# FPGA_Regulators.net
KiCad netlist of a schematic drawn in Altium Designer
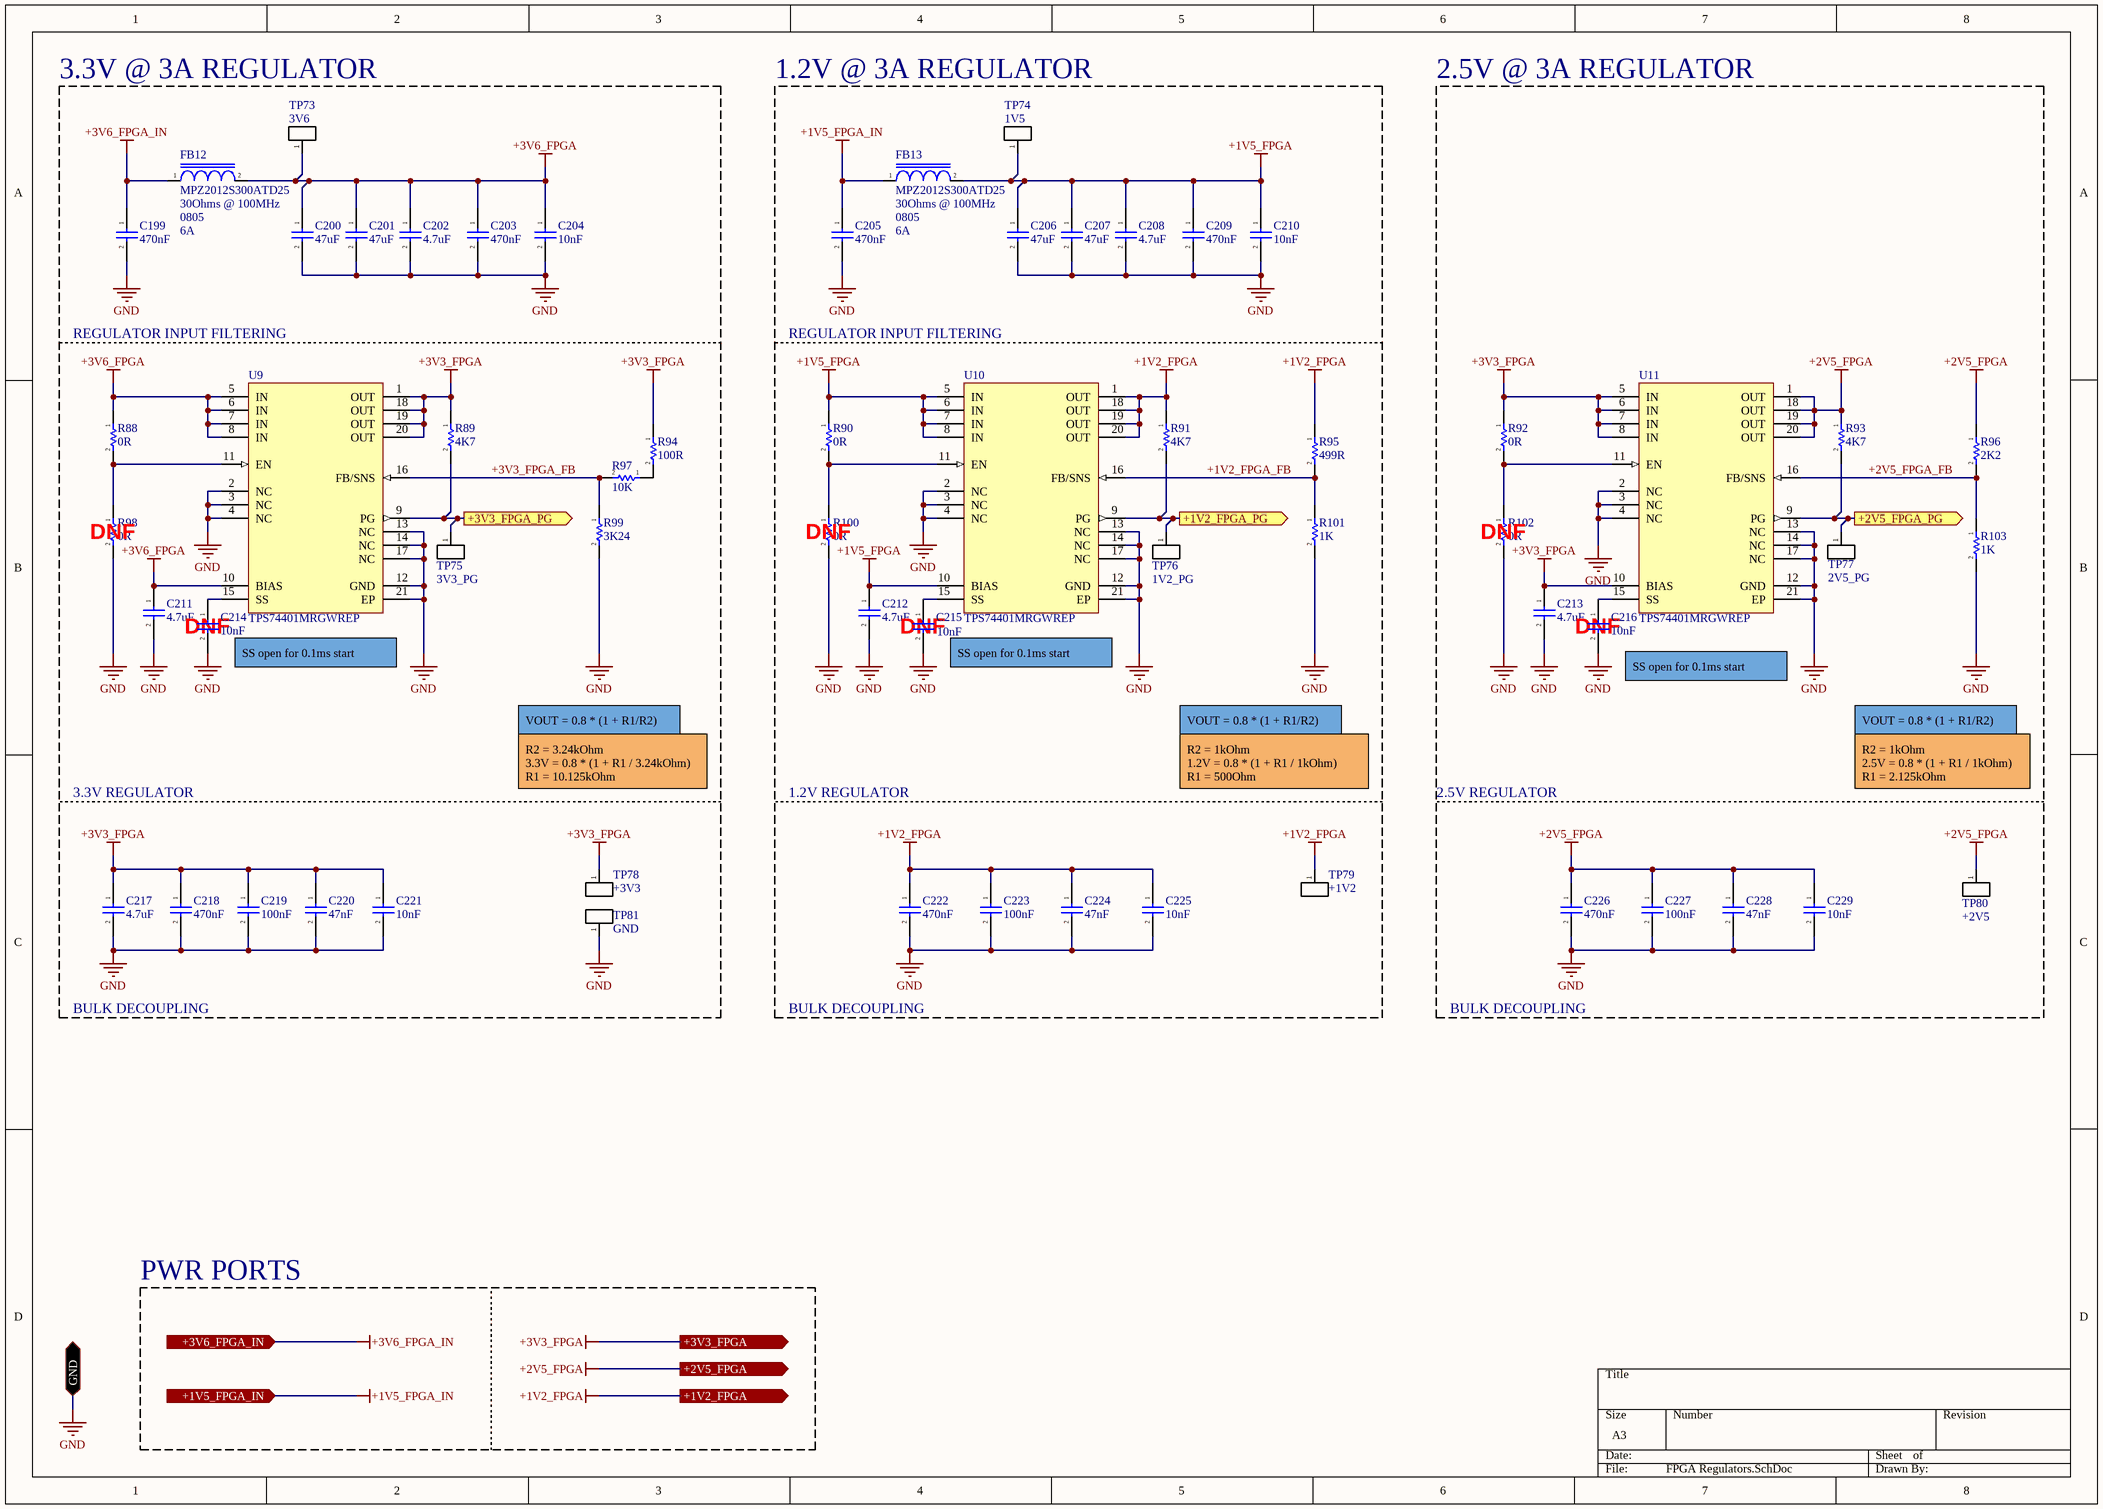
[diagram p0: FPGA Regulators.SchDoc]

(export (version "E")
  (design (tool "Eeschema 10.0.6"))
  (components
    (comp (ref "C199")
      (value "470nF")
      (footprint "CAP_0402")
      (description "Generic SMT Ceramic Capacitor")
      (libsource (lib "Symbols") (part "CAP_CER"))
    )
    (comp (ref "C200")
      (value "47uF")
      (footprint "CAP_1206")
      (description "Generic SMT Ceramic Capacitor")
      (libsource (lib "Symbols") (part "CAP_CER"))
    )
    (comp (ref "C201")
      (value "47uF")
      (footprint "CAP_1206")
      (description "Generic SMT Ceramic Capacitor")
      (libsource (lib "Symbols") (part "CAP_CER"))
    )
    (comp (ref "C202")
      (value "4.7uF")
      (footprint "CAP_0805")
      (description "Generic SMT Ceramic Capacitor")
      (libsource (lib "Symbols") (part "CAP_CER"))
    )
    (comp (ref "C203")
      (value "470nF")
      (footprint "CAP_0402")
      (description "Generic SMT Ceramic Capacitor")
      (libsource (lib "Symbols") (part "CAP_CER"))
    )
    (comp (ref "C204")
      (value "10nF")
      (footprint "CAP_0201")
      (description "Generic SMT Ceramic Capacitor")
      (libsource (lib "Symbols") (part "CAP_CER"))
    )
    (comp (ref "C205")
      (value "470nF")
      (footprint "CAP_0402")
      (description "Generic SMT Ceramic Capacitor")
      (libsource (lib "Symbols") (part "CAP_CER"))
    )
    (comp (ref "C206")
      (value "47uF")
      (footprint "CAP_1206")
      (description "Generic SMT Ceramic Capacitor")
      (libsource (lib "Symbols") (part "CAP_CER"))
    )
    (comp (ref "C207")
      (value "47uF")
      (footprint "CAP_1206")
      (description "Generic SMT Ceramic Capacitor")
      (libsource (lib "Symbols") (part "CAP_CER"))
    )
    (comp (ref "C208")
      (value "4.7uF")
      (footprint "CAP_0805")
      (description "Generic SMT Ceramic Capacitor")
      (libsource (lib "Symbols") (part "CAP_CER"))
    )
    (comp (ref "C209")
      (value "470nF")
      (footprint "CAP_0402")
      (description "Generic SMT Ceramic Capacitor")
      (libsource (lib "Symbols") (part "CAP_CER"))
    )
    (comp (ref "C210")
      (value "10nF")
      (footprint "CAP_0201")
      (description "Generic SMT Ceramic Capacitor")
      (libsource (lib "Symbols") (part "CAP_CER"))
    )
    (comp (ref "C211")
      (value "4.7uF")
      (footprint "CAP_0805")
      (description "Generic SMT Ceramic Capacitor")
      (libsource (lib "Symbols") (part "CAP_CER"))
    )
    (comp (ref "C212")
      (value "4.7uF")
      (footprint "CAP_0805")
      (description "Generic SMT Ceramic Capacitor")
      (libsource (lib "Symbols") (part "CAP_CER"))
    )
    (comp (ref "C213")
      (value "4.7uF")
      (footprint "CAP_0805")
      (description "Generic SMT Ceramic Capacitor")
      (libsource (lib "Symbols") (part "CAP_CER"))
    )
    (comp (ref "C214")
      (value "10nF")
      (footprint "CAP_0201")
      (description "Generic SMT Ceramic Capacitor")
      (libsource (lib "Symbols") (part "CAP_CER"))
    )
    (comp (ref "C215")
      (value "10nF")
      (footprint "CAP_0201")
      (description "Generic SMT Ceramic Capacitor")
      (libsource (lib "Symbols") (part "CAP_CER"))
    )
    (comp (ref "C216")
      (value "10nF")
      (footprint "CAP_0201")
      (description "Generic SMT Ceramic Capacitor")
      (libsource (lib "Symbols") (part "CAP_CER"))
    )
    (comp (ref "C217")
      (value "4.7uF")
      (footprint "CAP_0805")
      (description "Generic SMT Ceramic Capacitor")
      (libsource (lib "Symbols") (part "CAP_CER"))
    )
    (comp (ref "C218")
      (value "470nF")
      (footprint "CAP_0402")
      (description "Generic SMT Ceramic Capacitor")
      (libsource (lib "Symbols") (part "CAP_CER"))
    )
    (comp (ref "C219")
      (value "100nF")
      (footprint "CAP_0402")
      (description "Generic SMT Ceramic Capacitor")
      (libsource (lib "Symbols") (part "CAP_CER"))
    )
    (comp (ref "C220")
      (value "47nF")
      (footprint "CAP_0201")
      (description "Generic SMT Ceramic Capacitor")
      (libsource (lib "Symbols") (part "CAP_CER"))
    )
    (comp (ref "C221")
      (value "10nF")
      (footprint "CAP_0201")
      (description "Generic SMT Ceramic Capacitor")
      (libsource (lib "Symbols") (part "CAP_CER"))
    )
    (comp (ref "C222")
      (value "470nF")
      (footprint "CAP_0402")
      (description "Generic SMT Ceramic Capacitor")
      (libsource (lib "Symbols") (part "CAP_CER"))
    )
    (comp (ref "C223")
      (value "100nF")
      (footprint "CAP_0402")
      (description "Generic SMT Ceramic Capacitor")
      (libsource (lib "Symbols") (part "CAP_CER"))
    )
    (comp (ref "C224")
      (value "47nF")
      (footprint "CAP_0201")
      (description "Generic SMT Ceramic Capacitor")
      (libsource (lib "Symbols") (part "CAP_CER"))
    )
    (comp (ref "C225")
      (value "10nF")
      (footprint "CAP_0201")
      (description "Generic SMT Ceramic Capacitor")
      (libsource (lib "Symbols") (part "CAP_CER"))
    )
    (comp (ref "C226")
      (value "470nF")
      (footprint "CAP_0402")
      (description "Generic SMT Ceramic Capacitor")
      (libsource (lib "Symbols") (part "CAP_CER"))
    )
    (comp (ref "C227")
      (value "100nF")
      (footprint "CAP_0402")
      (description "Generic SMT Ceramic Capacitor")
      (libsource (lib "Symbols") (part "CAP_CER"))
    )
    (comp (ref "C228")
      (value "47nF")
      (footprint "CAP_0201")
      (description "Generic SMT Ceramic Capacitor")
      (libsource (lib "Symbols") (part "CAP_CER"))
    )
    (comp (ref "C229")
      (value "10nF")
      (footprint "CAP_0201")
      (description "Generic SMT Ceramic Capacitor")
      (libsource (lib "Symbols") (part "CAP_CER"))
    )
    (comp (ref "FB12")
      (value "MPZ2012S300ATD25")
      (footprint "Footprints:IND_0805")
      (description "30 Ohms @ 100 MHz 1 Power Line Ferrite Bead 0805 (2012 Metric) 6A 10mOhm")
      (fields
        (field (name "IMPEDANCE @ FREQ") "30Ohms @ 100MHz")
        (field (name "PACKAGE / CASE") "0805")
        (field (name "CURRENT RATING") "6A")
      )
      (libsource (lib "CryptLib") (part "IND_MPZ2012S300ATD25"))
    )
    (comp (ref "FB13")
      (value "MPZ2012S300ATD25")
      (footprint "Footprints:IND_0805")
      (description "30 Ohms @ 100 MHz 1 Power Line Ferrite Bead 0805 (2012 Metric) 6A 10mOhm")
      (fields
        (field (name "IMPEDANCE @ FREQ") "30Ohms @ 100MHz")
        (field (name "PACKAGE / CASE") "0805")
        (field (name "CURRENT RATING") "6A")
      )
      (libsource (lib "CryptLib") (part "IND_MPZ2012S300ATD25"))
    )
    (comp (ref "R88")
      (value "0R")
      (footprint "RES_0603")
      (description "Resistor")
      (fields (field (name "POWER") "1/8W") (field (name "TOLERANCE") "10%"))
      (libsource (lib "Symbols") (part "RESISTOR"))
    )
    (comp (ref "R89")
      (value "4K7")
      (footprint "RES_0603")
      (description "Resistor")
      (fields (field (name "POWER") "1/16W") (field (name "TOLERANCE") "10%"))
      (libsource (lib "Symbols") (part "RESISTOR"))
    )
    (comp (ref "R90")
      (value "0R")
      (footprint "RES_0603")
      (description "Resistor")
      (fields (field (name "POWER") "1/8W") (field (name "TOLERANCE") "10%"))
      (libsource (lib "Symbols") (part "RESISTOR"))
    )
    (comp (ref "R91")
      (value "4K7")
      (footprint "RES_0603")
      (description "Resistor")
      (fields (field (name "POWER") "1/16W") (field (name "TOLERANCE") "10%"))
      (libsource (lib "Symbols") (part "RESISTOR"))
    )
    (comp (ref "R92")
      (value "0R")
      (footprint "RES_0603")
      (description "Resistor")
      (fields (field (name "POWER") "1/8W") (field (name "TOLERANCE") "10%"))
      (libsource (lib "Symbols") (part "RESISTOR"))
    )
    (comp (ref "R93")
      (value "4K7")
      (footprint "RES_0603")
      (description "Resistor")
      (fields (field (name "POWER") "1/16W") (field (name "TOLERANCE") "10%"))
      (libsource (lib "Symbols") (part "RESISTOR"))
    )
    (comp (ref "R94")
      (value "100R")
      (footprint "RES_0402")
      (description "Resistor")
      (fields (field (name "POWER") "1/8W") (field (name "TOLERANCE") "10%"))
      (libsource (lib "Symbols") (part "RESISTOR"))
    )
    (comp (ref "R95")
      (value "499R")
      (footprint "RES_0402")
      (description "Resistor")
      (fields (field (name "POWER") "1/8W") (field (name "TOLERANCE") "1%"))
      (libsource (lib "Symbols") (part "RESISTOR"))
    )
    (comp (ref "R96")
      (value "2K2")
      (footprint "RES_0603")
      (description "Resistor")
      (fields (field (name "POWER") "1/16W") (field (name "TOLERANCE") "2%"))
      (libsource (lib "Symbols") (part "RESISTOR"))
    )
    (comp (ref "R97")
      (value "10K")
      (footprint "RES_0603")
      (description "Resistor")
      (fields (field (name "POWER") "1/16W") (field (name "TOLERANCE") "10%"))
      (libsource (lib "Symbols") (part "RESISTOR"))
    )
    (comp (ref "R98")
      (value "0R")
      (footprint "RES_0603")
      (description "Resistor")
      (fields (field (name "POWER") "1/8W") (field (name "TOLERANCE") "10%"))
      (libsource (lib "Symbols") (part "RESISTOR"))
    )
    (comp (ref "R99")
      (value "3K24")
      (footprint "RES_0603")
      (description "Resistor")
      (fields (field (name "POWER") "1/16W") (field (name "TOLERANCE") "2%"))
      (libsource (lib "Symbols") (part "RESISTOR"))
    )
    (comp (ref "R100")
      (value "0R")
      (footprint "RES_0603")
      (description "Resistor")
      (fields (field (name "POWER") "1/8W") (field (name "TOLERANCE") "10%"))
      (libsource (lib "Symbols") (part "RESISTOR"))
    )
    (comp (ref "R101")
      (value "1K")
      (footprint "RES_0603")
      (description "Resistor")
      (fields (field (name "POWER") "1/8W") (field (name "TOLERANCE") "5%"))
      (libsource (lib "Symbols") (part "RESISTOR"))
    )
    (comp (ref "R102")
      (value "0R")
      (footprint "RES_0603")
      (description "Resistor")
      (fields (field (name "POWER") "1/8W") (field (name "TOLERANCE") "10%"))
      (libsource (lib "Symbols") (part "RESISTOR"))
    )
    (comp (ref "R103")
      (value "1K")
      (footprint "RES_0603")
      (description "Resistor")
      (fields (field (name "POWER") "1/8W") (field (name "TOLERANCE") "5%"))
      (libsource (lib "Symbols") (part "RESISTOR"))
    )
    (comp (ref "TP73")
      (value "3V6")
      (footprint "TP_PAD")
      (description "Test Point")
      (libsource (lib "Symbols") (part "TESTPOINT"))
    )
    (comp (ref "TP74")
      (value "1V5")
      (footprint "TP_PAD")
      (description "Test Point")
      (libsource (lib "Symbols") (part "TESTPOINT"))
    )
    (comp (ref "TP75")
      (value "3V3_PG")
      (footprint "TP_PAD_TINY")
      (description "Test Point")
      (libsource (lib "Symbols") (part "TESTPOINT"))
    )
    (comp (ref "TP76")
      (value "1V2_PG")
      (footprint "TP_PAD_TINY")
      (description "Test Point")
      (libsource (lib "Symbols") (part "TESTPOINT"))
    )
    (comp (ref "TP77")
      (value "2V5_PG")
      (footprint "TP_PAD_TINY")
      (description "Test Point")
      (libsource (lib "Symbols") (part "TESTPOINT"))
    )
    (comp (ref "TP78")
      (value "+3V3")
      (footprint "TP_HOLE")
      (description "Test Point")
      (libsource (lib "Symbols") (part "TESTPOINT"))
    )
    (comp (ref "TP79")
      (value "+1V2")
      (footprint "TP_HOLE")
      (description "Test Point")
      (libsource (lib "Symbols") (part "TESTPOINT"))
    )
    (comp (ref "TP80")
      (value "+2V5")
      (footprint "TP_HOLE")
      (description "Test Point")
      (libsource (lib "Symbols") (part "TESTPOINT"))
    )
    (comp (ref "TP81")
      (value "GND")
      (footprint "TP_PAD_SMALL")
      (description "Test Point")
      (libsource (lib "Symbols") (part "TESTPOINT"))
    )
    (comp (ref "U9")
      (value "TPS74401MRGWREP")
      (footprint "TPS74401")
      (description "IC REG LINEAR POS ADJ 3A 20VQFN")
      (fields (field (name "MFR") "Texas Instruments") (field (name "DIGIKEY PART NUMBER") "296-27227-1-ND"))
      (libsource (lib "CryptLib") (part "IC_TPS47701"))
    )
    (comp (ref "U10")
      (value "TPS74401MRGWREP")
      (footprint "TPS74401")
      (description "IC REG LINEAR POS ADJ 3A 20VQFN")
      (fields (field (name "MFR") "Texas Instruments") (field (name "DIGIKEY PART NUMBER") "296-27227-1-ND"))
      (libsource (lib "CryptLib") (part "IC_TPS47701"))
    )
    (comp (ref "U11")
      (value "TPS74401MRGWREP")
      (footprint "TPS74401")
      (description "IC REG LINEAR POS ADJ 3A 20VQFN")
      (fields (field (name "MFR") "Texas Instruments") (field (name "DIGIKEY PART NUMBER") "296-27227-1-ND"))
      (libsource (lib "CryptLib") (part "IC_TPS47701"))
    )
  )
  (nets
    (net (code "1") (name "+1V2_FPGA") (class "Default")
      (node (ref "C222") (pin "1") (pinfunction "1_1") (pintype "passive"))
      (node (ref "C223") (pin "1") (pinfunction "1_1") (pintype "passive"))
      (node (ref "C224") (pin "1") (pinfunction "1_1") (pintype "passive"))
      (node (ref "C225") (pin "1") (pinfunction "1_1") (pintype "passive"))
      (node (ref "R91") (pin "1") (pinfunction "1_1") (pintype "passive"))
      (node (ref "R95") (pin "1") (pinfunction "1_1") (pintype "passive"))
      (node (ref "TP79") (pin "1") (pinfunction "A_1") (pintype "passive"))
      (node (ref "U10") (pin "1") (pinfunction "OUT_1") (pintype "power_in"))
      (node (ref "U10") (pin "18") (pinfunction "OUT_18") (pintype "power_in"))
      (node (ref "U10") (pin "19") (pinfunction "OUT_19") (pintype "power_in"))
      (node (ref "U10") (pin "20") (pinfunction "OUT_20") (pintype "power_in"))
    )
    (net (code "2") (name "+1V5_FPGA") (class "Default")
      (node (ref "C206") (pin "1") (pinfunction "1_1") (pintype "passive"))
      (node (ref "C207") (pin "1") (pinfunction "1_1") (pintype "passive"))
      (node (ref "C208") (pin "1") (pinfunction "1_1") (pintype "passive"))
      (node (ref "C209") (pin "1") (pinfunction "1_1") (pintype "passive"))
      (node (ref "C210") (pin "1") (pinfunction "1_1") (pintype "passive"))
      (node (ref "C212") (pin "1") (pinfunction "1_1") (pintype "passive"))
      (node (ref "FB13") (pin "2") (pinfunction "2_2") (pintype "passive"))
      (node (ref "R90") (pin "1") (pinfunction "1_1") (pintype "passive"))
      (node (ref "TP74") (pin "1") (pinfunction "A_1") (pintype "passive"))
      (node (ref "U10") (pin "10") (pinfunction "BIAS_10") (pintype "power_in"))
      (node (ref "U10") (pin "5") (pinfunction "IN_5") (pintype "power_in"))
      (node (ref "U10") (pin "6") (pinfunction "IN_6") (pintype "power_in"))
      (node (ref "U10") (pin "7") (pinfunction "IN_7") (pintype "power_in"))
      (node (ref "U10") (pin "8") (pinfunction "IN_8") (pintype "power_in"))
    )
    (net (code "3") (name "+1V5_FPGA_IN") (class "Default")
      (node (ref "C205") (pin "1") (pinfunction "1_1") (pintype "passive"))
      (node (ref "FB13") (pin "1") (pinfunction "1_1") (pintype "passive"))
    )
    (net (code "4") (name "+2V5_FPGA") (class "Default")
      (node (ref "C226") (pin "1") (pinfunction "1_1") (pintype "passive"))
      (node (ref "C227") (pin "1") (pinfunction "1_1") (pintype "passive"))
      (node (ref "C228") (pin "1") (pinfunction "1_1") (pintype "passive"))
      (node (ref "C229") (pin "1") (pinfunction "1_1") (pintype "passive"))
      (node (ref "R93") (pin "1") (pinfunction "1_1") (pintype "passive"))
      (node (ref "R96") (pin "1") (pinfunction "1_1") (pintype "passive"))
      (node (ref "TP80") (pin "1") (pinfunction "A_1") (pintype "passive"))
      (node (ref "U11") (pin "1") (pinfunction "OUT_1") (pintype "power_in"))
      (node (ref "U11") (pin "18") (pinfunction "OUT_18") (pintype "power_in"))
      (node (ref "U11") (pin "19") (pinfunction "OUT_19") (pintype "power_in"))
      (node (ref "U11") (pin "20") (pinfunction "OUT_20") (pintype "power_in"))
    )
    (net (code "5") (name "+3V3_FPGA") (class "Default")
      (node (ref "C213") (pin "1") (pinfunction "1_1") (pintype "passive"))
      (node (ref "C217") (pin "1") (pinfunction "1_1") (pintype "passive"))
      (node (ref "C218") (pin "1") (pinfunction "1_1") (pintype "passive"))
      (node (ref "C219") (pin "1") (pinfunction "1_1") (pintype "passive"))
      (node (ref "C220") (pin "1") (pinfunction "1_1") (pintype "passive"))
      (node (ref "C221") (pin "1") (pinfunction "1_1") (pintype "passive"))
      (node (ref "R89") (pin "1") (pinfunction "1_1") (pintype "passive"))
      (node (ref "R92") (pin "1") (pinfunction "1_1") (pintype "passive"))
      (node (ref "R94") (pin "1") (pinfunction "1_1") (pintype "passive"))
      (node (ref "TP78") (pin "1") (pinfunction "A_1") (pintype "passive"))
      (node (ref "U11") (pin "10") (pinfunction "BIAS_10") (pintype "power_in"))
      (node (ref "U11") (pin "5") (pinfunction "IN_5") (pintype "power_in"))
      (node (ref "U11") (pin "6") (pinfunction "IN_6") (pintype "power_in"))
      (node (ref "U11") (pin "7") (pinfunction "IN_7") (pintype "power_in"))
      (node (ref "U11") (pin "8") (pinfunction "IN_8") (pintype "power_in"))
      (node (ref "U9") (pin "1") (pinfunction "OUT_1") (pintype "power_in"))
      (node (ref "U9") (pin "18") (pinfunction "OUT_18") (pintype "power_in"))
      (node (ref "U9") (pin "19") (pinfunction "OUT_19") (pintype "power_in"))
      (node (ref "U9") (pin "20") (pinfunction "OUT_20") (pintype "power_in"))
    )
    (net (code "6") (name "+3V6_FPGA") (class "Default")
      (node (ref "C200") (pin "1") (pinfunction "1_1") (pintype "passive"))
      (node (ref "C201") (pin "1") (pinfunction "1_1") (pintype "passive"))
      (node (ref "C202") (pin "1") (pinfunction "1_1") (pintype "passive"))
      (node (ref "C203") (pin "1") (pinfunction "1_1") (pintype "passive"))
      (node (ref "C204") (pin "1") (pinfunction "1_1") (pintype "passive"))
      (node (ref "C211") (pin "1") (pinfunction "1_1") (pintype "passive"))
      (node (ref "FB12") (pin "2") (pinfunction "2_2") (pintype "passive"))
      (node (ref "R88") (pin "1") (pinfunction "1_1") (pintype "passive"))
      (node (ref "TP73") (pin "1") (pinfunction "A_1") (pintype "passive"))
      (node (ref "U9") (pin "10") (pinfunction "BIAS_10") (pintype "power_in"))
      (node (ref "U9") (pin "5") (pinfunction "IN_5") (pintype "power_in"))
      (node (ref "U9") (pin "6") (pinfunction "IN_6") (pintype "power_in"))
      (node (ref "U9") (pin "7") (pinfunction "IN_7") (pintype "power_in"))
      (node (ref "U9") (pin "8") (pinfunction "IN_8") (pintype "power_in"))
    )
    (net (code "7") (name "+3V6_FPGA_IN") (class "Default")
      (node (ref "C199") (pin "1") (pinfunction "1_1") (pintype "passive"))
      (node (ref "FB12") (pin "1") (pinfunction "1_1") (pintype "passive"))
    )
    (net (code "8") (name "/+1V2_FPGA_FB") (class "Default")
      (node (ref "R101") (pin "1") (pinfunction "1_1") (pintype "passive"))
      (node (ref "R95") (pin "2") (pinfunction "2_2") (pintype "passive"))
      (node (ref "U10") (pin "16") (pinfunction "FB/SNS_16") (pintype "input"))
    )
    (net (code "9") (name "/+1V2_FPGA_PG") (class "Default")
      (node (ref "R91") (pin "2") (pinfunction "2_2") (pintype "passive"))
      (node (ref "TP76") (pin "1") (pinfunction "A_1") (pintype "passive"))
      (node (ref "U10") (pin "9") (pinfunction "PG_9") (pintype "output"))
    )
    (net (code "10") (name "/+2V5_FPGA_FB") (class "Default")
      (node (ref "R103") (pin "1") (pinfunction "1_1") (pintype "passive"))
      (node (ref "R96") (pin "2") (pinfunction "2_2") (pintype "passive"))
      (node (ref "U11") (pin "16") (pinfunction "FB/SNS_16") (pintype "input"))
    )
    (net (code "11") (name "/+2V5_FPGA_PG") (class "Default")
      (node (ref "R93") (pin "2") (pinfunction "2_2") (pintype "passive"))
      (node (ref "TP77") (pin "1") (pinfunction "A_1") (pintype "passive"))
      (node (ref "U11") (pin "9") (pinfunction "PG_9") (pintype "output"))
    )
    (net (code "12") (name "/+3V3_FPGA_FB") (class "Default")
      (node (ref "R97") (pin "2") (pinfunction "2_2") (pintype "passive"))
      (node (ref "R99") (pin "1") (pinfunction "1_1") (pintype "passive"))
      (node (ref "U9") (pin "16") (pinfunction "FB/SNS_16") (pintype "input"))
    )
    (net (code "13") (name "/+3V3_FPGA_PG") (class "Default")
      (node (ref "R89") (pin "2") (pinfunction "2_2") (pintype "passive"))
      (node (ref "TP75") (pin "1") (pinfunction "A_1") (pintype "passive"))
      (node (ref "U9") (pin "9") (pinfunction "PG_9") (pintype "output"))
    )
    (net (code "14") (name "GND") (class "Default")
      (node (ref "C199") (pin "2") (pinfunction "2_2") (pintype "passive"))
      (node (ref "C200") (pin "2") (pinfunction "2_2") (pintype "passive"))
      (node (ref "C201") (pin "2") (pinfunction "2_2") (pintype "passive"))
      (node (ref "C202") (pin "2") (pinfunction "2_2") (pintype "passive"))
      (node (ref "C203") (pin "2") (pinfunction "2_2") (pintype "passive"))
      (node (ref "C204") (pin "2") (pinfunction "2_2") (pintype "passive"))
      (node (ref "C205") (pin "2") (pinfunction "2_2") (pintype "passive"))
      (node (ref "C206") (pin "2") (pinfunction "2_2") (pintype "passive"))
      (node (ref "C207") (pin "2") (pinfunction "2_2") (pintype "passive"))
      (node (ref "C208") (pin "2") (pinfunction "2_2") (pintype "passive"))
      (node (ref "C209") (pin "2") (pinfunction "2_2") (pintype "passive"))
      (node (ref "C210") (pin "2") (pinfunction "2_2") (pintype "passive"))
      (node (ref "C211") (pin "2") (pinfunction "2_2") (pintype "passive"))
      (node (ref "C212") (pin "2") (pinfunction "2_2") (pintype "passive"))
      (node (ref "C213") (pin "2") (pinfunction "2_2") (pintype "passive"))
      (node (ref "C214") (pin "2") (pinfunction "2_2") (pintype "passive"))
      (node (ref "C215") (pin "2") (pinfunction "2_2") (pintype "passive"))
      (node (ref "C216") (pin "2") (pinfunction "2_2") (pintype "passive"))
      (node (ref "C217") (pin "2") (pinfunction "2_2") (pintype "passive"))
      (node (ref "C218") (pin "2") (pinfunction "2_2") (pintype "passive"))
      (node (ref "C219") (pin "2") (pinfunction "2_2") (pintype "passive"))
      (node (ref "C220") (pin "2") (pinfunction "2_2") (pintype "passive"))
      (node (ref "C221") (pin "2") (pinfunction "2_2") (pintype "passive"))
      (node (ref "C222") (pin "2") (pinfunction "2_2") (pintype "passive"))
      (node (ref "C223") (pin "2") (pinfunction "2_2") (pintype "passive"))
      (node (ref "C224") (pin "2") (pinfunction "2_2") (pintype "passive"))
      (node (ref "C225") (pin "2") (pinfunction "2_2") (pintype "passive"))
      (node (ref "C226") (pin "2") (pinfunction "2_2") (pintype "passive"))
      (node (ref "C227") (pin "2") (pinfunction "2_2") (pintype "passive"))
      (node (ref "C228") (pin "2") (pinfunction "2_2") (pintype "passive"))
      (node (ref "C229") (pin "2") (pinfunction "2_2") (pintype "passive"))
      (node (ref "R100") (pin "2") (pinfunction "2_2") (pintype "passive"))
      (node (ref "R101") (pin "2") (pinfunction "2_2") (pintype "passive"))
      (node (ref "R102") (pin "2") (pinfunction "2_2") (pintype "passive"))
      (node (ref "R103") (pin "2") (pinfunction "2_2") (pintype "passive"))
      (node (ref "R98") (pin "2") (pinfunction "2_2") (pintype "passive"))
      (node (ref "R99") (pin "2") (pinfunction "2_2") (pintype "passive"))
      (node (ref "TP81") (pin "1") (pinfunction "A_1") (pintype "passive"))
      (node (ref "U10") (pin "12") (pinfunction "GND_12") (pintype "power_in"))
      (node (ref "U10") (pin "13") (pinfunction "NC_13") (pintype "passive"))
      (node (ref "U10") (pin "14") (pinfunction "NC_14") (pintype "passive"))
      (node (ref "U10") (pin "17") (pinfunction "NC_17") (pintype "passive"))
      (node (ref "U10") (pin "2") (pinfunction "NC_2") (pintype "passive"))
      (node (ref "U10") (pin "21") (pinfunction "EP_21") (pintype "power_in"))
      (node (ref "U10") (pin "3") (pinfunction "NC_3") (pintype "passive"))
      (node (ref "U10") (pin "4") (pinfunction "NC_4") (pintype "passive"))
      (node (ref "U11") (pin "12") (pinfunction "GND_12") (pintype "power_in"))
      (node (ref "U11") (pin "13") (pinfunction "NC_13") (pintype "passive"))
      (node (ref "U11") (pin "14") (pinfunction "NC_14") (pintype "passive"))
      (node (ref "U11") (pin "17") (pinfunction "NC_17") (pintype "passive"))
      (node (ref "U11") (pin "2") (pinfunction "NC_2") (pintype "passive"))
      (node (ref "U11") (pin "21") (pinfunction "EP_21") (pintype "power_in"))
      (node (ref "U11") (pin "3") (pinfunction "NC_3") (pintype "passive"))
      (node (ref "U11") (pin "4") (pinfunction "NC_4") (pintype "passive"))
      (node (ref "U9") (pin "12") (pinfunction "GND_12") (pintype "power_in"))
      (node (ref "U9") (pin "13") (pinfunction "NC_13") (pintype "passive"))
      (node (ref "U9") (pin "14") (pinfunction "NC_14") (pintype "passive"))
      (node (ref "U9") (pin "17") (pinfunction "NC_17") (pintype "passive"))
      (node (ref "U9") (pin "2") (pinfunction "NC_2") (pintype "passive"))
      (node (ref "U9") (pin "21") (pinfunction "EP_21") (pintype "power_in"))
      (node (ref "U9") (pin "3") (pinfunction "NC_3") (pintype "passive"))
      (node (ref "U9") (pin "4") (pinfunction "NC_4") (pintype "passive"))
    )
    (net (code "15") (name "Net-(R94-Pad2)") (class "Default")
      (node (ref "R94") (pin "2") (pinfunction "2_2") (pintype "passive"))
      (node (ref "R97") (pin "1") (pinfunction "1_1") (pintype "passive"))
    )
    (net (code "16") (name "Net-(U9-EN)") (class "Default")
      (node (ref "R88") (pin "2") (pinfunction "2_2") (pintype "passive"))
      (node (ref "R98") (pin "1") (pinfunction "1_1") (pintype "passive"))
      (node (ref "U9") (pin "11") (pinfunction "EN_11") (pintype "input"))
    )
    (net (code "17") (name "Net-(U9-SS)") (class "Default")
      (node (ref "C214") (pin "1") (pinfunction "1_1") (pintype "passive"))
      (node (ref "U9") (pin "15") (pinfunction "SS_15") (pintype "passive"))
    )
    (net (code "18") (name "Net-(U10-EN)") (class "Default")
      (node (ref "R100") (pin "1") (pinfunction "1_1") (pintype "passive"))
      (node (ref "R90") (pin "2") (pinfunction "2_2") (pintype "passive"))
      (node (ref "U10") (pin "11") (pinfunction "EN_11") (pintype "input"))
    )
    (net (code "19") (name "Net-(U10-SS)") (class "Default")
      (node (ref "C215") (pin "1") (pinfunction "1_1") (pintype "passive"))
      (node (ref "U10") (pin "15") (pinfunction "SS_15") (pintype "passive"))
    )
    (net (code "20") (name "Net-(U11-EN)") (class "Default")
      (node (ref "R102") (pin "1") (pinfunction "1_1") (pintype "passive"))
      (node (ref "R92") (pin "2") (pinfunction "2_2") (pintype "passive"))
      (node (ref "U11") (pin "11") (pinfunction "EN_11") (pintype "input"))
    )
    (net (code "21") (name "Net-(U11-SS)") (class "Default")
      (node (ref "C216") (pin "1") (pinfunction "1_1") (pintype "passive"))
      (node (ref "U11") (pin "15") (pinfunction "SS_15") (pintype "passive"))
    )
  )
)
